# PiHome_Temp_Sensors.net
KiCad netlist of a schematic drawn in EAGLE
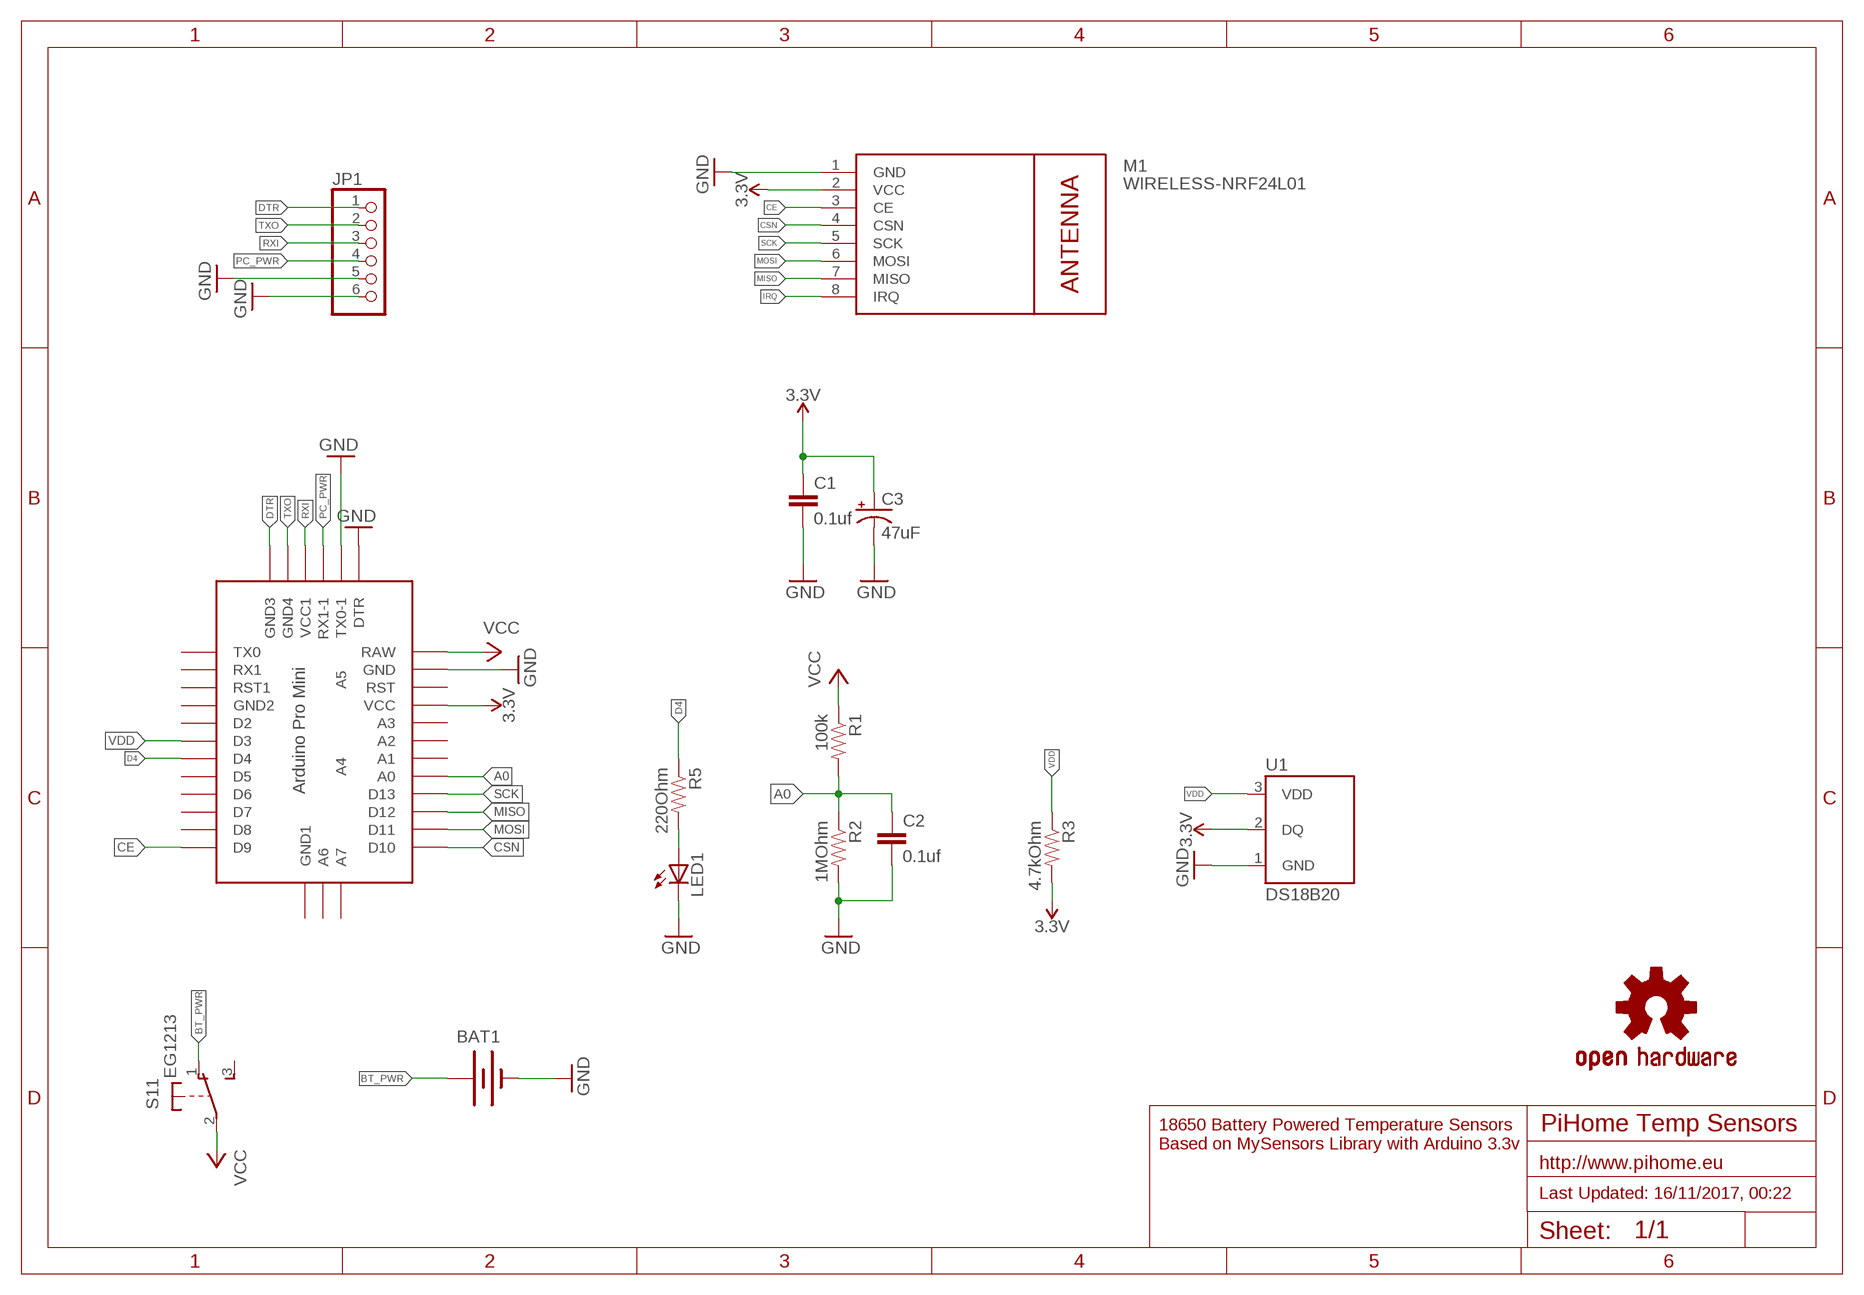
[diagram p0: schematic, sheet 1]

(export (version "E")
  (design (tool "Eeschema 10.0.6"))
  (components
    (comp (ref "BAT1")
      (value "BATTERY18650")
      (footprint "eagle-import:BATTERY_18650-HOLDER")
      (libsource (lib "eagle-import") (part "BATTERY18650"))
    )
    (comp (ref "C1")
      (value "0.1uf")
      (footprint "eagle-import:CAP-PTH-SMALL-KIT")
      (libsource (lib "eagle-import") (part "0.1UF-50V-20%(PTH)KIT-EZ"))
    )
    (comp (ref "C2")
      (value "0.1uf")
      (footprint "eagle-import:CAP-PTH-SMALL-KIT")
      (libsource (lib "eagle-import") (part "0.1UF-50V-20%(PTH)KIT-EZ"))
    )
    (comp (ref "C3")
      (value "47uF")
      (footprint "eagle-import:CPOL-RADIAL-10UF-25V-KIT")
      (libsource (lib "eagle-import") (part "10UF-25V-20%(PTH)KIT"))
    )
    (comp (ref "JP1")
      (value "PINHD-1X6")
      (footprint "eagle-import:1X06")
      (libsource (lib "eagle-import") (part "PINHD-1X6"))
    )
    (comp (ref "LED1")
      (value "LED3MM")
      (footprint "eagle-import:LED3MM")
      (libsource (lib "eagle-import") (part "LED3MM"))
    )
    (comp (ref "LOGO1")
      (value "OSHW-LOGOL")
      (footprint "eagle-import:OSHW-LOGO-L")
      (libsource (lib "eagle-import") (part "OSHW-LOGOL"))
    )
    (comp (ref "M1")
      (value "WIRELESS-NRF24L01")
      (footprint "eagle-import:WIRELESS-NRF24L01")
      (libsource (lib "eagle-import") (part "WIRELESS-NRF24L01"))
    )
    (comp (ref "R1")
      (value "100k")
      (footprint "eagle-import:AXIAL-0.3")
      (libsource (lib "eagle-import") (part "100KOHM-1/4W-5%(PTH)"))
    )
    (comp (ref "R2")
      (value "1MOhm")
      (footprint "eagle-import:AXIAL-0.3")
      (libsource (lib "eagle-import") (part "RESISTORAXIAL-0.3"))
    )
    (comp (ref "R3")
      (value "4.7kOhm")
      (footprint "eagle-import:AXIAL-0.3")
      (libsource (lib "eagle-import") (part "RESISTORAXIAL-0.3"))
    )
    (comp (ref "R5")
      (value "220Ohm")
      (footprint "eagle-import:AXIAL-0.3")
      (libsource (lib "eagle-import") (part "RESISTORAXIAL-0.3"))
    )
    (comp (ref "S1")
      (value "EG1213")
      (footprint "eagle-import:EG1213")
      (libsource (lib "eagle-import") (part "EG1213"))
    )
    (comp (ref "U$1")
      (value "ABK-PRO-MINI")
      (footprint "eagle-import:ABK-PRO-MINI")
      (libsource (lib "eagle-import") (part "ABK-PRO-MINI"))
    )
    (comp (ref "U1")
      (value "DS18B20")
      (footprint "eagle-import:TO-92-AMMO")
      (libsource (lib "eagle-import") (part "DS18B20"))
    )
  )
  (nets
    (net (code "1") (name "3.3V") (class "Default")
      (node (ref "C1") (pin "1") (pinfunction "1_1") (pintype "passive"))
      (node (ref "C3") (pin "1") (pinfunction "+_1") (pintype "passive"))
      (node (ref "M1") (pin "2") (pinfunction "VCC_2") (pintype "power_in"))
      (node (ref "R3") (pin "P$2") (pinfunction "2_P$2") (pintype "passive"))
      (node (ref "U$1") (pin "VCC") (pinfunction "VCC_VCC") (pintype "bidirectional"))
      (node (ref "U1") (pin "2") (pinfunction "DQ_2") (pintype "bidirectional"))
    )
    (net (code "2") (name "A0") (class "Default")
      (node (ref "C2") (pin "1") (pinfunction "1_1") (pintype "passive"))
      (node (ref "R1") (pin "P$2") (pinfunction "2_P$2") (pintype "passive"))
      (node (ref "R2") (pin "P$1") (pinfunction "1_P$1") (pintype "passive"))
      (node (ref "U$1") (pin "A0") (pinfunction "A0_A0") (pintype "bidirectional"))
    )
    (net (code "3") (name "BT_PWR") (class "Default")
      (node (ref "BAT1") (pin "PWR@1") (pinfunction "+_PWR@1") (pintype "power_in"))
      (node (ref "S1") (pin "1") (pinfunction "O_1") (pintype "passive"))
    )
    (net (code "4") (name "CE") (class "Default")
      (node (ref "M1") (pin "3") (pinfunction "CE_3") (pintype "bidirectional"))
      (node (ref "U$1") (pin "D9") (pinfunction "D9_D9") (pintype "bidirectional"))
    )
    (net (code "5") (name "CSN") (class "Default")
      (node (ref "M1") (pin "4") (pinfunction "CSN_4") (pintype "bidirectional"))
      (node (ref "U$1") (pin "D10") (pinfunction "D10_D10") (pintype "bidirectional"))
    )
    (net (code "6") (name "D4") (class "Default")
      (node (ref "R5") (pin "P$1") (pinfunction "1_P$1") (pintype "passive"))
      (node (ref "U$1") (pin "D4") (pinfunction "D4_D4") (pintype "bidirectional"))
    )
    (net (code "7") (name "DTR") (class "Default")
      (node (ref "JP1") (pin "1") (pinfunction "1_1") (pintype "passive"))
      (node (ref "U$1") (pin "GND2") (pinfunction "GND3_GND2") (pintype "bidirectional"))
    )
    (net (code "8") (name "GND") (class "Default")
      (node (ref "BAT1") (pin "GND@1") (pinfunction "-_GND@1") (pintype "power_in"))
      (node (ref "C1") (pin "2") (pinfunction "2_2") (pintype "passive"))
      (node (ref "C2") (pin "2") (pinfunction "2_2") (pintype "passive"))
      (node (ref "C3") (pin "2") (pinfunction "-_2") (pintype "passive"))
      (node (ref "JP1") (pin "5") (pinfunction "5_5") (pintype "passive"))
      (node (ref "JP1") (pin "6") (pinfunction "6_6") (pintype "passive"))
      (node (ref "LED1") (pin "K") (pinfunction "C_K") (pintype "passive"))
      (node (ref "M1") (pin "1") (pinfunction "GND_1") (pintype "power_in"))
      (node (ref "R2") (pin "P$2") (pinfunction "2_P$2") (pintype "passive"))
      (node (ref "U$1") (pin "DTR") (pinfunction "DTR_DTR") (pintype "bidirectional"))
      (node (ref "U$1") (pin "GND") (pinfunction "GND_GND") (pintype "bidirectional"))
      (node (ref "U$1") (pin "TX0-1") (pinfunction "TX0-1_TX0-1") (pintype "bidirectional"))
      (node (ref "U1") (pin "1") (pinfunction "GND_1") (pintype "power_in"))
    )
    (net (code "9") (name "IRQ") (class "Default")
      (node (ref "M1") (pin "8") (pinfunction "IRQ_8") (pintype "bidirectional"))
    )
    (net (code "10") (name "MISO") (class "Default")
      (node (ref "M1") (pin "7") (pinfunction "MISO_7") (pintype "bidirectional"))
      (node (ref "U$1") (pin "D12") (pinfunction "D12_D12") (pintype "bidirectional"))
    )
    (net (code "11") (name "MOSI") (class "Default")
      (node (ref "M1") (pin "6") (pinfunction "MOSI_6") (pintype "bidirectional"))
      (node (ref "U$1") (pin "D11") (pinfunction "D11_D11") (pintype "bidirectional"))
    )
    (net (code "12") (name "Net-(R5-2)") (class "Default")
      (node (ref "LED1") (pin "A") (pinfunction "A_A") (pintype "passive"))
      (node (ref "R5") (pin "P$2") (pinfunction "2_P$2") (pintype "passive"))
    )
    (net (code "13") (name "PC_PWR") (class "Default")
      (node (ref "JP1") (pin "4") (pinfunction "4_4") (pintype "passive"))
      (node (ref "U$1") (pin "RX1-1") (pinfunction "RX1-1_RX1-1") (pintype "bidirectional"))
    )
    (net (code "14") (name "RXI") (class "Default")
      (node (ref "JP1") (pin "3") (pinfunction "3_3") (pintype "passive"))
      (node (ref "U$1") (pin "VCC1") (pinfunction "VCC1_VCC1") (pintype "bidirectional"))
    )
    (net (code "15") (name "SCK") (class "Default")
      (node (ref "M1") (pin "5") (pinfunction "SCK_5") (pintype "bidirectional"))
      (node (ref "U$1") (pin "D13") (pinfunction "D13_D13") (pintype "bidirectional"))
    )
    (net (code "16") (name "TXO") (class "Default")
      (node (ref "JP1") (pin "2") (pinfunction "2_2") (pintype "passive"))
      (node (ref "U$1") (pin "GND3") (pinfunction "GND4_GND3") (pintype "bidirectional"))
    )
    (net (code "17") (name "VCC") (class "Default")
      (node (ref "R1") (pin "P$1") (pinfunction "1_P$1") (pintype "passive"))
      (node (ref "S1") (pin "2") (pinfunction "P_2") (pintype "passive"))
      (node (ref "U$1") (pin "RAW") (pinfunction "RAW_RAW") (pintype "bidirectional"))
    )
    (net (code "18") (name "VDD") (class "Default")
      (node (ref "R3") (pin "P$1") (pinfunction "1_P$1") (pintype "passive"))
      (node (ref "U$1") (pin "D3") (pinfunction "D3_D3") (pintype "bidirectional"))
      (node (ref "U1") (pin "3") (pinfunction "VDD_3") (pintype "power_in"))
    )
    (net (code "19") (name "unconnected-(S1A-S-Pad3)") (class "Default")
      (node (ref "S1") (pin "3") (pinfunction "S_3") (pintype "passive"))
    )
    (net (code "20") (name "unconnected-(U$1-GND1-PadGND4)") (class "Default")
      (node (ref "U$1") (pin "GND4") (pinfunction "GND1_GND4") (pintype "bidirectional"))
    )
    (net (code "21") (name "unconnected-(U$1-GND2-PadGND1)") (class "Default")
      (node (ref "U$1") (pin "GND1") (pinfunction "GND2_GND1") (pintype "bidirectional"))
    )
    (net (code "22") (name "unconnected-(U$1-PadA1)") (class "Default")
      (node (ref "U$1") (pin "A1") (pinfunction "A1_A1") (pintype "bidirectional"))
    )
    (net (code "23") (name "unconnected-(U$1-PadA2)") (class "Default")
      (node (ref "U$1") (pin "A2") (pinfunction "A2_A2") (pintype "bidirectional"))
    )
    (net (code "24") (name "unconnected-(U$1-PadA3)") (class "Default")
      (node (ref "U$1") (pin "A3") (pinfunction "A3_A3") (pintype "bidirectional"))
    )
    (net (code "25") (name "unconnected-(U$1-PadA4)") (class "Default")
      (node (ref "U$1") (pin "A4") (pinfunction "A4_A4") (pintype "bidirectional"))
    )
    (net (code "26") (name "unconnected-(U$1-PadA5)") (class "Default")
      (node (ref "U$1") (pin "A5") (pinfunction "A5_A5") (pintype "bidirectional"))
    )
    (net (code "27") (name "unconnected-(U$1-PadA6)") (class "Default")
      (node (ref "U$1") (pin "A6") (pinfunction "A6_A6") (pintype "bidirectional"))
    )
    (net (code "28") (name "unconnected-(U$1-PadA7)") (class "Default")
      (node (ref "U$1") (pin "A7") (pinfunction "A7_A7") (pintype "bidirectional"))
    )
    (net (code "29") (name "unconnected-(U$1-PadD2)") (class "Default")
      (node (ref "U$1") (pin "D2") (pinfunction "D2_D2") (pintype "bidirectional"))
    )
    (net (code "30") (name "unconnected-(U$1-PadD5)") (class "Default")
      (node (ref "U$1") (pin "D5") (pinfunction "D5_D5") (pintype "bidirectional"))
    )
    (net (code "31") (name "unconnected-(U$1-PadD6)") (class "Default")
      (node (ref "U$1") (pin "D6") (pinfunction "D6_D6") (pintype "bidirectional"))
    )
    (net (code "32") (name "unconnected-(U$1-PadD7)") (class "Default")
      (node (ref "U$1") (pin "D7") (pinfunction "D7_D7") (pintype "bidirectional"))
    )
    (net (code "33") (name "unconnected-(U$1-PadD8)") (class "Default")
      (node (ref "U$1") (pin "D8") (pinfunction "D8_D8") (pintype "bidirectional"))
    )
    (net (code "34") (name "unconnected-(U$1-PadRST)") (class "Default")
      (node (ref "U$1") (pin "RST") (pinfunction "RST_RST") (pintype "bidirectional"))
    )
    (net (code "35") (name "unconnected-(U$1-PadRST1)") (class "Default")
      (node (ref "U$1") (pin "RST1") (pinfunction "RST1_RST1") (pintype "bidirectional"))
    )
    (net (code "36") (name "unconnected-(U$1-PadRX1)") (class "Default")
      (node (ref "U$1") (pin "RX1") (pinfunction "RX1_RX1") (pintype "bidirectional"))
    )
    (net (code "37") (name "unconnected-(U$1-PadTX0)") (class "Default")
      (node (ref "U$1") (pin "TX0") (pinfunction "TX0_TX0") (pintype "bidirectional"))
    )
  )
)
